# PulseSensor.net
KiCad netlist of a schematic drawn in EAGLE
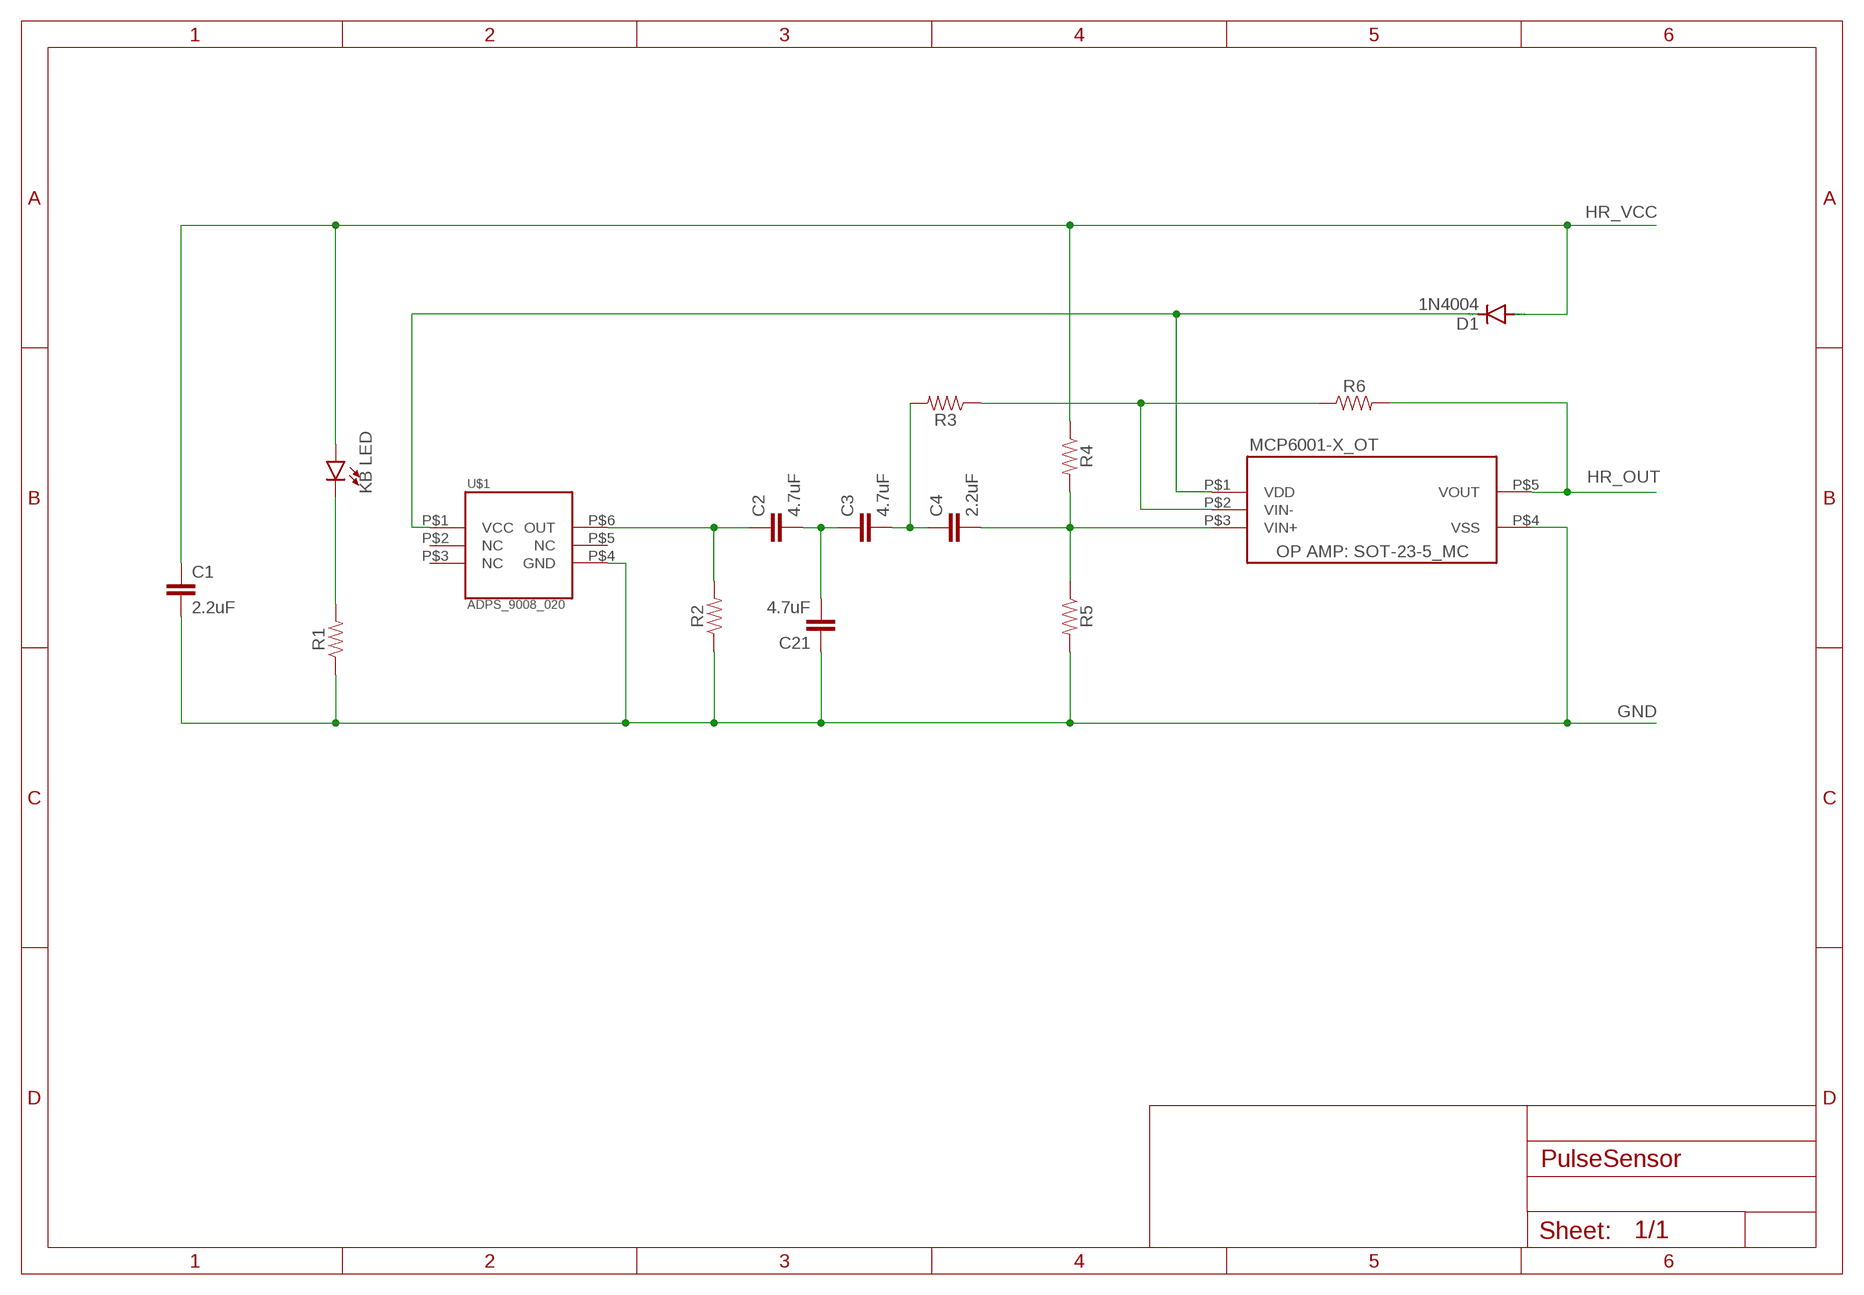
[diagram p0: schematic, sheet 1]

(export (version "E")
  (design (tool "Eeschema 10.0.6"))
  (components
    (comp (ref "C1")
      (value "2.2uF")
      (footprint "eagle-import:0603")
      (libsource (lib "eagle-import") (part "2.2UF-0603-10V-20%"))
    )
    (comp (ref "C2")
      (value "4.7uF")
      (footprint "eagle-import:0603")
      (libsource (lib "eagle-import") (part "4.7UF0603"))
    )
    (comp (ref "C3")
      (value "4.7uF")
      (footprint "eagle-import:0603")
      (libsource (lib "eagle-import") (part "4.7UF0603"))
    )
    (comp (ref "C4")
      (value "2.2uF")
      (footprint "eagle-import:0603")
      (libsource (lib "eagle-import") (part "2.2UF-0603-10V-20%"))
    )
    (comp (ref "C21")
      (value "4.7uF")
      (footprint "eagle-import:0603")
      (libsource (lib "eagle-import") (part "4.7UF0603"))
    )
    (comp (ref "D1")
      (value "1N4004")
      (footprint "eagle-import:DO41-10")
      (libsource (lib "eagle-import") (part "1N4004"))
    )
    (comp (ref "R1")
      (value "RESISTOR0603")
      (footprint "eagle-import:0603")
      (libsource (lib "eagle-import") (part "RESISTOR0603"))
    )
    (comp (ref "R2")
      (value "RESISTOR0603")
      (footprint "eagle-import:0603")
      (libsource (lib "eagle-import") (part "RESISTOR0603"))
    )
    (comp (ref "R3")
      (value "RESISTOR0603")
      (footprint "eagle-import:0603")
      (libsource (lib "eagle-import") (part "RESISTOR0603"))
    )
    (comp (ref "R4")
      (value "RESISTOR0603")
      (footprint "eagle-import:0603")
      (libsource (lib "eagle-import") (part "RESISTOR0603"))
    )
    (comp (ref "R5")
      (value "RESISTOR0603")
      (footprint "eagle-import:0603")
      (libsource (lib "eagle-import") (part "RESISTOR0603"))
    )
    (comp (ref "R6")
      (value "RESISTOR0603")
      (footprint "eagle-import:0603")
      (libsource (lib "eagle-import") (part "RESISTOR0603"))
    )
    (comp (ref "U$1")
      (value "ADPS_9008_020")
      (footprint "eagle-import:ADPS_FP")
      (libsource (lib "eagle-import") (part "ADPS_9008_020"))
    )
    (comp (ref "U$2")
      (value "KB_REVMNT_LED")
      (footprint "eagle-import:REVMNT_LED_FP")
      (libsource (lib "eagle-import") (part "KB_REVMNT_LED"))
    )
    (comp (ref "U$3")
      (value "MCP6001-X_SOT-23-5")
      (footprint "eagle-import:SOT-23-5")
      (libsource (lib "eagle-import") (part "MCP6001-X_SOT-23-5"))
    )
  )
  (nets
    (net (code "1") (name "/GND") (class "Default")
      (node (ref "C1") (pin "2") (pinfunction "2_2") (pintype "passive"))
      (node (ref "C21") (pin "1") (pinfunction "1_1") (pintype "passive"))
      (node (ref "R1") (pin "1") (pinfunction "1_1") (pintype "passive"))
      (node (ref "R2") (pin "1") (pinfunction "1_1") (pintype "passive"))
      (node (ref "R5") (pin "2") (pinfunction "2_2") (pintype "passive"))
      (node (ref "U$1") (pin "P$4") (pinfunction "GND_P$4") (pintype "power_in"))
      (node (ref "U$3") (pin "P$4") (pinfunction "VSS_P$4") (pintype "power_in"))
    )
    (net (code "2") (name "/HR_OUT") (class "Default")
      (node (ref "R6") (pin "2") (pinfunction "2_2") (pintype "passive"))
      (node (ref "U$3") (pin "P$5") (pinfunction "VOUT_P$5") (pintype "output"))
    )
    (net (code "3") (name "/HR_VCC") (class "Default")
      (node (ref "C1") (pin "1") (pinfunction "1_1") (pintype "passive"))
      (node (ref "D1") (pin "A") (pinfunction "A_A") (pintype "passive"))
      (node (ref "R4") (pin "1") (pinfunction "1_1") (pintype "passive"))
      (node (ref "U$2") (pin "P$1") (pinfunction "A_P$1") (pintype "passive"))
    )
    (net (code "4") (name "Net-(C2-Pad2)") (class "Default")
      (node (ref "C2") (pin "2") (pinfunction "2_2") (pintype "passive"))
      (node (ref "C21") (pin "2") (pinfunction "2_2") (pintype "passive"))
      (node (ref "C3") (pin "1") (pinfunction "1_1") (pintype "passive"))
    )
    (net (code "5") (name "Net-(C3-Pad2)") (class "Default")
      (node (ref "C3") (pin "2") (pinfunction "2_2") (pintype "passive"))
      (node (ref "C4") (pin "1") (pinfunction "1_1") (pintype "passive"))
      (node (ref "R3") (pin "2") (pinfunction "2_2") (pintype "passive"))
    )
    (net (code "6") (name "Net-(U$1-OUT)") (class "Default")
      (node (ref "C2") (pin "1") (pinfunction "1_1") (pintype "passive"))
      (node (ref "R2") (pin "2") (pinfunction "2_2") (pintype "passive"))
      (node (ref "U$1") (pin "P$6") (pinfunction "OUT_P$6") (pintype "output"))
    )
    (net (code "7") (name "Net-(U$1-VCC)") (class "Default")
      (node (ref "D1") (pin "C") (pinfunction "C_C") (pintype "passive"))
      (node (ref "U$1") (pin "P$1") (pinfunction "VCC_P$1") (pintype "power_in"))
      (node (ref "U$3") (pin "P$1") (pinfunction "VDD_P$1") (pintype "power_in"))
    )
    (net (code "8") (name "Net-(U$2-C)") (class "Default")
      (node (ref "R1") (pin "2") (pinfunction "2_2") (pintype "passive"))
      (node (ref "U$2") (pin "P$2") (pinfunction "C_P$2") (pintype "passive"))
    )
    (net (code "9") (name "Net-(U$3-VIN+)") (class "Default")
      (node (ref "C4") (pin "2") (pinfunction "2_2") (pintype "passive"))
      (node (ref "R4") (pin "2") (pinfunction "2_2") (pintype "passive"))
      (node (ref "R5") (pin "1") (pinfunction "1_1") (pintype "passive"))
      (node (ref "U$3") (pin "P$3") (pinfunction "VIN+_P$3") (pintype "input"))
    )
    (net (code "10") (name "Net-(U$3-VIN-)") (class "Default")
      (node (ref "R3") (pin "1") (pinfunction "1_1") (pintype "passive"))
      (node (ref "R6") (pin "1") (pinfunction "1_1") (pintype "passive"))
      (node (ref "U$3") (pin "P$2") (pinfunction "VIN-_P$2") (pintype "input"))
    )
    (net (code "11") (name "unconnected-(U$1-NC-PadP$2)") (class "Default")
      (node (ref "U$1") (pin "P$2") (pinfunction "NC_P$2") (pintype "bidirectional"))
    )
    (net (code "12") (name "unconnected-(U$1-NC-PadP$3)") (class "Default")
      (node (ref "U$1") (pin "P$3") (pinfunction "NC_P$3") (pintype "bidirectional"))
    )
    (net (code "13") (name "unconnected-(U$1-NC-PadP$5)") (class "Default")
      (node (ref "U$1") (pin "P$5") (pinfunction "NC_P$5") (pintype "bidirectional"))
    )
  )
)
